# Sensors.net
KiCad netlist of a schematic drawn in Altium Designer
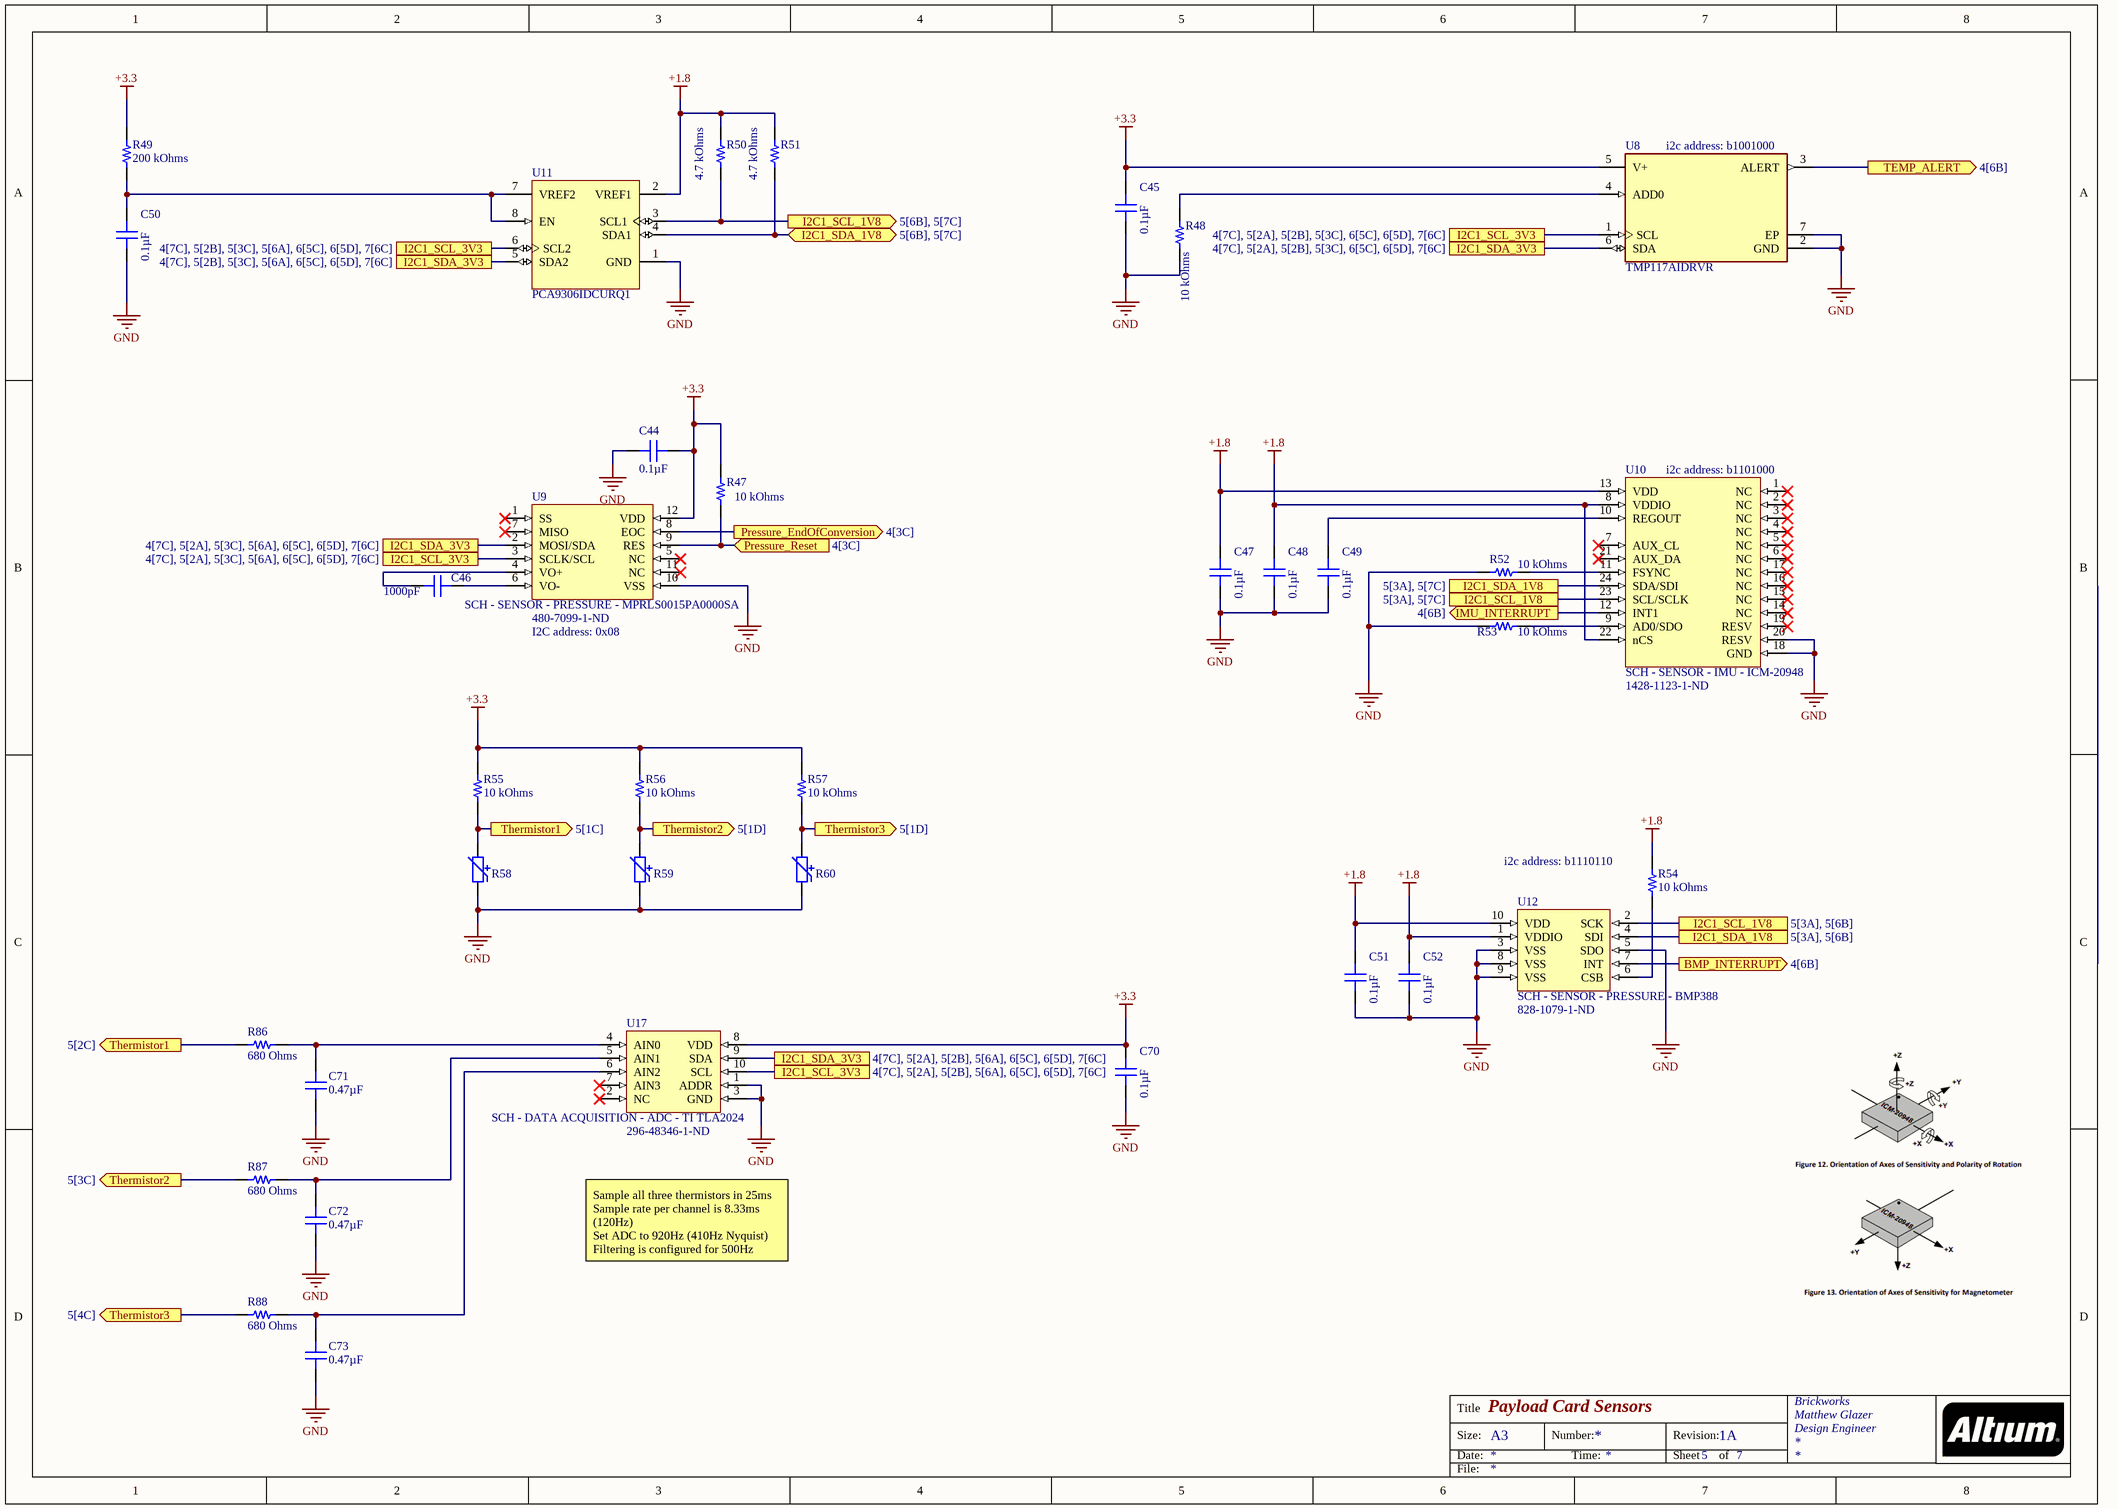
[diagram p0: Sensors.SchDoc]

(export (version "E")
  (design (tool "Eeschema 10.0.6"))
  (components
    (comp (ref "C44")
      (value "0.1µF")
      (footprint "CAP 0603_1608")
      (description "CAP CER 0.1UF 25V X7R 0603")
      (fields
        (field (name "PART NUMBER") "CL10B104KA8WPNC")
        (field (name "MANUFACTURER") "Samsung Electro-Mechanics")
      )
      (libsource (lib "Celestial Altium Library - altium_library") (part "Capacitor"))
    )
    (comp (ref "C45")
      (value "0.1µF")
      (footprint "CAP 0603_1608")
      (description "CAP CER 0.1UF 25V X7R 0603")
      (fields
        (field (name "PART NUMBER") "CL10B104KA8WPNC")
        (field (name "MANUFACTURER") "Samsung Electro-Mechanics")
      )
      (libsource (lib "Celestial Altium Library - altium_library") (part "Capacitor"))
    )
    (comp (ref "C46")
      (value "1000pF")
      (footprint "CAP 0603_1608")
      (description "CAP CER 1000PF 16V X7R 0603")
      (fields (field (name "PART NUMBER") "0603YC102JAT2A") (field (name "MANUFACTURER") "AVX Corporation"))
      (libsource (lib "Celestial Altium Library - altium_library") (part "Capacitor"))
    )
    (comp (ref "C47")
      (value "0.1µF")
      (footprint "CAP 0603_1608")
      (description "CAP CER 0.1UF 25V X7R 0603")
      (fields
        (field (name "PART NUMBER") "CL10B104KA8WPNC")
        (field (name "MANUFACTURER") "Samsung Electro-Mechanics")
      )
      (libsource (lib "Celestial Altium Library - altium_library") (part "Capacitor"))
    )
    (comp (ref "C48")
      (value "0.1µF")
      (footprint "CAP 0603_1608")
      (description "CAP CER 0.1UF 25V X7R 0603")
      (fields
        (field (name "PART NUMBER") "CL10B104KA8WPNC")
        (field (name "MANUFACTURER") "Samsung Electro-Mechanics")
      )
      (libsource (lib "Celestial Altium Library - altium_library") (part "Capacitor"))
    )
    (comp (ref "C49")
      (value "0.1µF")
      (footprint "CAP 0603_1608")
      (description "CAP CER 0.1UF 25V X7R 0603")
      (fields
        (field (name "PART NUMBER") "CL10B104KA8WPNC")
        (field (name "MANUFACTURER") "Samsung Electro-Mechanics")
      )
      (libsource (lib "Celestial Altium Library - altium_library") (part "Capacitor"))
    )
    (comp (ref "C50")
      (value "0.1µF")
      (footprint "CAP 0603_1608")
      (description "CAP CER 0.1UF 25V X7R 0603")
      (fields
        (field (name "PART NUMBER") "CL10B104KA8WPNC")
        (field (name "MANUFACTURER") "Samsung Electro-Mechanics")
      )
      (libsource (lib "Celestial Altium Library - altium_library") (part "Capacitor"))
    )
    (comp (ref "C51")
      (value "0.1µF")
      (footprint "CAP 0603_1608")
      (description "CAP CER 0.1UF 25V X7R 0603")
      (fields
        (field (name "PART NUMBER") "CL10B104KA8WPNC")
        (field (name "MANUFACTURER") "Samsung Electro-Mechanics")
      )
      (libsource (lib "Celestial Altium Library - altium_library") (part "Capacitor"))
    )
    (comp (ref "C52")
      (value "0.1µF")
      (footprint "CAP 0603_1608")
      (description "CAP CER 0.1UF 25V X7R 0603")
      (fields
        (field (name "PART NUMBER") "CL10B104KA8WPNC")
        (field (name "MANUFACTURER") "Samsung Electro-Mechanics")
      )
      (libsource (lib "Celestial Altium Library - altium_library") (part "Capacitor"))
    )
    (comp (ref "C70")
      (value "0.1µF")
      (footprint "CAP 0603_1608")
      (description "CAP CER 0.1UF 25V X7R 0603")
      (fields
        (field (name "PART NUMBER") "CL10B104KA8WPNC")
        (field (name "MANUFACTURER") "Samsung Electro-Mechanics")
      )
      (libsource (lib "Celestial Altium Library - altium_library") (part "Capacitor"))
    )
    (comp (ref "C71")
      (value "0.47µF")
      (footprint "CAP 0603_1608")
      (description "CAP CER 0.47UF 16V X5R 0603")
      (fields (field (name "PART NUMBER") "C0603C474K4PACTU") (field (name "MANUFACTURER") "KEMET"))
      (libsource (lib "Celestial Altium Library - altium_library") (part "Capacitor"))
    )
    (comp (ref "C72")
      (value "0.47µF")
      (footprint "CAP 0603_1608")
      (description "CAP CER 0.47UF 16V X5R 0603")
      (fields (field (name "PART NUMBER") "C0603C474K4PACTU") (field (name "MANUFACTURER") "KEMET"))
      (libsource (lib "Celestial Altium Library - altium_library") (part "Capacitor"))
    )
    (comp (ref "C73")
      (value "0.47µF")
      (footprint "CAP 0603_1608")
      (description "CAP CER 0.47UF 16V X5R 0603")
      (fields (field (name "PART NUMBER") "C0603C474K4PACTU") (field (name "MANUFACTURER") "KEMET"))
      (libsource (lib "Celestial Altium Library - altium_library") (part "Capacitor"))
    )
    (comp (ref "R47")
      (value "10 kOhms")
      (footprint "RES 0603_1608")
      (description "RES 10K OHM 5% 1/10W 0603")
      (fields
        (field (name "PART NUMBER") "RMCF0603JT10K0")
        (field (name "MANUFACTURER") "Stackpole Electronics Inc")
      )
      (libsource (lib "Celestial Altium Library - altium_library") (part "Resistor"))
    )
    (comp (ref "R48")
      (value "10 kOhms")
      (footprint "RES 0603_1608")
      (description "RES 10K OHM 5% 1/10W 0603")
      (fields
        (field (name "PART NUMBER") "RMCF0603JT10K0")
        (field (name "MANUFACTURER") "Stackpole Electronics Inc")
      )
      (libsource (lib "Celestial Altium Library - altium_library") (part "Resistor"))
    )
    (comp (ref "R49")
      (value "200 kOhms")
      (footprint "RES 0603_1608")
      (description "RES 200K OHM 1% 1/10W 0603")
      (fields
        (field (name "PART NUMBER") "RMCF0603FT200K")
        (field (name "MANUFACTURER") "Stackpole Electronics Inc")
      )
      (libsource (lib "Celestial Altium Library - altium_library") (part "Resistor"))
    )
    (comp (ref "R50")
      (value "4.7 kOhms")
      (footprint "RES 0603_1608")
      (description "RES 4.7K OHM 1% 1/10W 0603")
      (fields
        (field (name "PART NUMBER") "RMCF0603FT4K70")
        (field (name "MANUFACTURER") "Stackpole Electronics Inc")
      )
      (libsource (lib "Celestial Altium Library - altium_library") (part "Resistor"))
    )
    (comp (ref "R51")
      (value "4.7 kOhms")
      (footprint "RES 0603_1608")
      (description "RES 4.7K OHM 1% 1/10W 0603")
      (fields
        (field (name "PART NUMBER") "RMCF0603FT4K70")
        (field (name "MANUFACTURER") "Stackpole Electronics Inc")
      )
      (libsource (lib "Celestial Altium Library - altium_library") (part "Resistor"))
    )
    (comp (ref "R52")
      (value "10 kOhms")
      (footprint "RES 0603_1608")
      (description "RES 10K OHM 5% 1/10W 0603")
      (fields
        (field (name "PART NUMBER") "RMCF0603JT10K0")
        (field (name "MANUFACTURER") "Stackpole Electronics Inc")
      )
      (libsource (lib "Celestial Altium Library - altium_library") (part "Resistor"))
    )
    (comp (ref "R53")
      (value "10 kOhms")
      (footprint "RES 0603_1608")
      (description "RES 10K OHM 5% 1/10W 0603")
      (fields
        (field (name "PART NUMBER") "RMCF0603JT10K0")
        (field (name "MANUFACTURER") "Stackpole Electronics Inc")
      )
      (libsource (lib "Celestial Altium Library - altium_library") (part "Resistor"))
    )
    (comp (ref "R54")
      (value "10 kOhms")
      (footprint "RES 0603_1608")
      (description "RES 10K OHM 5% 1/10W 0603")
      (fields
        (field (name "PART NUMBER") "RMCF0603JT10K0")
        (field (name "MANUFACTURER") "Stackpole Electronics Inc")
      )
      (libsource (lib "Celestial Altium Library - altium_library") (part "Resistor"))
    )
    (comp (ref "R55")
      (value "10 kOhms")
      (footprint "RES 0603_1608")
      (description "RES 10K OHM 1% 1/10W 0603")
      (fields
        (field (name "PART NUMBER") "RMCF0603FT10K0")
        (field (name "MANUFACTURER") "Stackpole Electronics Inc")
      )
      (libsource (lib "Celestial Altium Library - altium_library") (part "Resistor"))
    )
    (comp (ref "R56")
      (value "10 kOhms")
      (footprint "RES 0603_1608")
      (description "RES 10K OHM 1% 1/10W 0603")
      (fields
        (field (name "PART NUMBER") "RMCF0603FT10K0")
        (field (name "MANUFACTURER") "Stackpole Electronics Inc")
      )
      (libsource (lib "Celestial Altium Library - altium_library") (part "Resistor"))
    )
    (comp (ref "R57")
      (value "10 kOhms")
      (footprint "RES 0603_1608")
      (description "RES 10K OHM 1% 1/10W 0603")
      (fields
        (field (name "PART NUMBER") "RMCF0603FT10K0")
        (field (name "MANUFACTURER") "Stackpole Electronics Inc")
      )
      (libsource (lib "Celestial Altium Library - altium_library") (part "Resistor"))
    )
    (comp (ref "R58")
      (value "10 kOhms")
      (footprint "PTC 0402_1005")
      (description "SENSOR PTC 10KOHM 1% X1SON")
      (fields (field (name "MANUFACTURER") "Texas Instruments") (field (name "PART NUMBER") "TMP6131DECR"))
      (libsource (lib "Celestial Altium Library - altium_library") (part "Thermistor PTC"))
    )
    (comp (ref "R59")
      (value "10 kOhms")
      (footprint "PTC 0402_1005")
      (description "SENSOR PTC 10KOHM 1% X1SON")
      (fields (field (name "MANUFACTURER") "Texas Instruments") (field (name "PART NUMBER") "TMP6131DECR"))
      (libsource (lib "Celestial Altium Library - altium_library") (part "Thermistor PTC"))
    )
    (comp (ref "R60")
      (value "10 kOhms")
      (footprint "PTC 0402_1005")
      (description "SENSOR PTC 10KOHM 1% X1SON")
      (fields (field (name "MANUFACTURER") "Texas Instruments") (field (name "PART NUMBER") "TMP6131DECR"))
      (libsource (lib "Celestial Altium Library - altium_library") (part "Thermistor PTC"))
    )
    (comp (ref "R86")
      (value "680 Ohms")
      (footprint "RES 0603_1608")
      (description "RES 680 OHM 1% 1/10W 0603")
      (fields
        (field (name "PART NUMBER") "RMCF0603FT680R")
        (field (name "MANUFACTURER") "Stackpole Electronics Inc")
      )
      (libsource (lib "Celestial Altium Library - altium_library") (part "Resistor"))
    )
    (comp (ref "R87")
      (value "680 Ohms")
      (footprint "RES 0603_1608")
      (description "RES 680 OHM 1% 1/10W 0603")
      (fields
        (field (name "PART NUMBER") "RMCF0603FT680R")
        (field (name "MANUFACTURER") "Stackpole Electronics Inc")
      )
      (libsource (lib "Celestial Altium Library - altium_library") (part "Resistor"))
    )
    (comp (ref "R88")
      (value "680 Ohms")
      (footprint "RES 0603_1608")
      (description "RES 680 OHM 1% 1/10W 0603")
      (fields
        (field (name "PART NUMBER") "RMCF0603FT680R")
        (field (name "MANUFACTURER") "Stackpole Electronics Inc")
      )
      (libsource (lib "Celestial Altium Library - altium_library") (part "Resistor"))
    )
    (comp (ref "U8")
      (value "TMP117AIDRVR")
      (footprint "FP-DRV0006A-MFG")
      (description "TEMPERATURE SENSOR")
      (fields
        (field (name "OCTOPART") "https://octopart.com/tmp117aidrvr-texas+instruments-95511044")
        (field (name "MANUFACTURER") "Texas Instruments")
      )
      (libsource (lib "Altium Content Vault") (part "bceab6869a9cb85cf5675529ee35ce4"))
    )
    (comp (ref "U9")
      (value "SCH - SENSOR - PRESSURE - MPRLS0015PA0000SA")
      (footprint "PCB - LEADLESS - SMD - Honeywell SMD12")
      (fields (field (name "SUPPLIER PART NUMBER 1") "480-7099-1-ND"))
      (libsource (lib "HAB_ICs") (part "SCH - SENSOR - PRESSURE - MPRLS0015PA0000SA"))
    )
    (comp (ref "U10")
      (value "SCH - SENSOR - IMU - ICM-20948")
      (footprint "PCB - LEADLESS - QFN - TDK 24-TFQFN")
      (fields (field (name "SUPPLIER PART NUMBER 1") "1428-1123-1-ND"))
      (libsource (lib "HAB_ICs") (part "SCH - SENSOR - IMU - ICM-20948"))
    )
    (comp (ref "U11")
      (value "PCA9306IDCURQ1")
      (footprint "DCU0008A_M")
      (fields (field (name "MANUFACTURER") "Texas Instruments"))
      (libsource (lib "Altium Content Vault") (part "TI-PCA9306-Q1-US8_DCU-8"))
    )
    (comp (ref "U12")
      (value "SCH - SENSOR - PRESSURE - BMP388")
      (footprint "PCB - LEADLESS - BOSCH LGA10")
      (fields (field (name "SUPPLIER PART NUMBER 1") "828-1079-1-ND"))
      (libsource (lib "HAB_ICs") (part "SCH - SENSOR - PRESSURE - BMP388"))
    )
    (comp (ref "U17")
      (value "SCH - DATA ACQUISITION - ADC - TI TLA2024")
      (footprint "PCB - LEADLESS - QFN - TI X2QFN-10")
      (fields (field (name "SUPPLIER PART NUMBER 1") "296-48346-1-ND"))
      (libsource (lib "HAB_ICs") (part "SCH - DATA ACQUISITION - ADC - TI TLA2024"))
    )
  )
  (nets
    (net (code "1") (name "+1.8") (class "Default")
      (node (ref "C47") (pin "2") (pinfunction "2_2") (pintype "passive"))
      (node (ref "C48") (pin "2") (pinfunction "2_2") (pintype "passive"))
      (node (ref "C51") (pin "2") (pinfunction "2_2") (pintype "passive"))
      (node (ref "C52") (pin "2") (pinfunction "2_2") (pintype "passive"))
      (node (ref "R50") (pin "2") (pinfunction "2_2") (pintype "passive"))
      (node (ref "R51") (pin "2") (pinfunction "2_2") (pintype "passive"))
      (node (ref "R54") (pin "1") (pinfunction "1_1") (pintype "passive"))
      (node (ref "U10") (pin "13") (pinfunction "VDD_13") (pintype "input"))
      (node (ref "U10") (pin "22") (pinfunction "nCS_22") (pintype "input"))
      (node (ref "U10") (pin "8") (pinfunction "VDDIO_8") (pintype "input"))
      (node (ref "U11") (pin "2") (pinfunction "VREF1_2") (pintype "power_in"))
      (node (ref "U12") (pin "1") (pinfunction "VDDIO_1") (pintype "input"))
      (node (ref "U12") (pin "10") (pinfunction "VDD_10") (pintype "input"))
    )
    (net (code "2") (name "+3.3") (class "Default")
      (node (ref "C44") (pin "1") (pinfunction "1_1") (pintype "passive"))
      (node (ref "C45") (pin "2") (pinfunction "2_2") (pintype "passive"))
      (node (ref "C70") (pin "2") (pinfunction "2_2") (pintype "passive"))
      (node (ref "R47") (pin "2") (pinfunction "2_2") (pintype "passive"))
      (node (ref "R49") (pin "2") (pinfunction "2_2") (pintype "passive"))
      (node (ref "R55") (pin "2") (pinfunction "2_2") (pintype "passive"))
      (node (ref "R56") (pin "2") (pinfunction "2_2") (pintype "passive"))
      (node (ref "R57") (pin "2") (pinfunction "2_2") (pintype "passive"))
      (node (ref "U17") (pin "8") (pinfunction "VDD_8") (pintype "input"))
      (node (ref "U8") (pin "5") (pinfunction "V+_5") (pintype "power_in"))
      (node (ref "U9") (pin "12") (pinfunction "VDD_12") (pintype "input"))
    )
    (net (code "3") (name "/BMP_INTERRUPT") (class "Default")
      (node (ref "U12") (pin "7") (pinfunction "INT_7") (pintype "input"))
    )
    (net (code "4") (name "/I2C1_SCL_1V8") (class "Default")
      (node (ref "R50") (pin "1") (pinfunction "1_1") (pintype "passive"))
      (node (ref "U10") (pin "23") (pinfunction "SCL/SCLK_23") (pintype "input"))
      (node (ref "U11") (pin "3") (pinfunction "SCL1_3") (pintype "bidirectional"))
      (node (ref "U12") (pin "2") (pinfunction "SCK_2") (pintype "input"))
    )
    (net (code "5") (name "/I2C1_SCL_3V3") (class "Default")
      (node (ref "U11") (pin "6") (pinfunction "SCL2_6") (pintype "bidirectional"))
      (node (ref "U17") (pin "10") (pinfunction "SCL_10") (pintype "input"))
      (node (ref "U8") (pin "1") (pinfunction "SCL_1") (pintype "input"))
      (node (ref "U9") (pin "3") (pinfunction "SCLK/SCL_3") (pintype "input"))
    )
    (net (code "6") (name "/I2C1_SDA_1V8") (class "Default")
      (node (ref "R51") (pin "1") (pinfunction "1_1") (pintype "passive"))
      (node (ref "U10") (pin "24") (pinfunction "SDA/SDI_24") (pintype "input"))
      (node (ref "U11") (pin "4") (pinfunction "SDA1_4") (pintype "bidirectional"))
      (node (ref "U12") (pin "4") (pinfunction "SDI_4") (pintype "input"))
    )
    (net (code "7") (name "/I2C1_SDA_3V3") (class "Default")
      (node (ref "U11") (pin "5") (pinfunction "SDA2_5") (pintype "bidirectional"))
      (node (ref "U17") (pin "9") (pinfunction "SDA_9") (pintype "input"))
      (node (ref "U8") (pin "6") (pinfunction "SDA_6") (pintype "bidirectional"))
      (node (ref "U9") (pin "2") (pinfunction "MOSI/SDA_2") (pintype "input"))
    )
    (net (code "8") (name "/IMU_INTERRUPT") (class "Default")
      (node (ref "U10") (pin "12") (pinfunction "INT1_12") (pintype "input"))
    )
    (net (code "9") (name "/Pressure_EndOfConversion") (class "Default")
      (node (ref "U9") (pin "8") (pinfunction "EOC_8") (pintype "input"))
    )
    (net (code "10") (name "/Pressure_Reset") (class "Default")
      (node (ref "R47") (pin "1") (pinfunction "1_1") (pintype "passive"))
      (node (ref "U9") (pin "9") (pinfunction "RES_9") (pintype "input"))
    )
    (net (code "11") (name "/TEMP_ALERT") (class "Default")
      (node (ref "U8") (pin "3") (pinfunction "ALERT_3") (pintype "output"))
    )
    (net (code "12") (name "/Thermistor1") (class "Default")
      (node (ref "R55") (pin "1") (pinfunction "1_1") (pintype "passive"))
      (node (ref "R58") (pin "2") (pinfunction "2_2") (pintype "passive"))
      (node (ref "R86") (pin "1") (pinfunction "1_1") (pintype "passive"))
    )
    (net (code "13") (name "/Thermistor2") (class "Default")
      (node (ref "R56") (pin "1") (pinfunction "1_1") (pintype "passive"))
      (node (ref "R59") (pin "2") (pinfunction "2_2") (pintype "passive"))
      (node (ref "R87") (pin "1") (pinfunction "1_1") (pintype "passive"))
    )
    (net (code "14") (name "/Thermistor3") (class "Default")
      (node (ref "R57") (pin "1") (pinfunction "1_1") (pintype "passive"))
      (node (ref "R60") (pin "2") (pinfunction "2_2") (pintype "passive"))
      (node (ref "R88") (pin "1") (pinfunction "1_1") (pintype "passive"))
    )
    (net (code "15") (name "GND") (class "Default")
      (node (ref "C44") (pin "2") (pinfunction "2_2") (pintype "passive"))
      (node (ref "C45") (pin "1") (pinfunction "1_1") (pintype "passive"))
      (node (ref "C47") (pin "1") (pinfunction "1_1") (pintype "passive"))
      (node (ref "C48") (pin "1") (pinfunction "1_1") (pintype "passive"))
      (node (ref "C49") (pin "1") (pinfunction "1_1") (pintype "passive"))
      (node (ref "C50") (pin "1") (pinfunction "1_1") (pintype "passive"))
      (node (ref "C51") (pin "1") (pinfunction "1_1") (pintype "passive"))
      (node (ref "C52") (pin "1") (pinfunction "1_1") (pintype "passive"))
      (node (ref "C70") (pin "1") (pinfunction "1_1") (pintype "passive"))
      (node (ref "C71") (pin "1") (pinfunction "1_1") (pintype "passive"))
      (node (ref "C72") (pin "1") (pinfunction "1_1") (pintype "passive"))
      (node (ref "C73") (pin "1") (pinfunction "1_1") (pintype "passive"))
      (node (ref "R48") (pin "1") (pinfunction "1_1") (pintype "passive"))
      (node (ref "R52") (pin "2") (pinfunction "2_2") (pintype "passive"))
      (node (ref "R53") (pin "2") (pinfunction "2_2") (pintype "passive"))
      (node (ref "R58") (pin "1") (pinfunction "1_1") (pintype "passive"))
      (node (ref "R59") (pin "1") (pinfunction "1_1") (pintype "passive"))
      (node (ref "R60") (pin "1") (pinfunction "1_1") (pintype "passive"))
      (node (ref "U10") (pin "18") (pinfunction "GND_18") (pintype "input"))
      (node (ref "U10") (pin "20") (pinfunction "RESV_20") (pintype "input"))
      (node (ref "U11") (pin "1") (pinfunction "GND_1") (pintype "power_in"))
      (node (ref "U12") (pin "3") (pinfunction "VSS_3") (pintype "input"))
      (node (ref "U12") (pin "5") (pinfunction "SDO_5") (pintype "input"))
      (node (ref "U12") (pin "8") (pinfunction "VSS_8") (pintype "input"))
      (node (ref "U12") (pin "9") (pinfunction "VSS_9") (pintype "input"))
      (node (ref "U17") (pin "1") (pinfunction "ADDR_1") (pintype "input"))
      (node (ref "U17") (pin "3") (pinfunction "GND_3") (pintype "input"))
      (node (ref "U8") (pin "2") (pinfunction "GND_2") (pintype "power_in"))
      (node (ref "U8") (pin "7") (pinfunction "EP_7") (pintype "passive"))
      (node (ref "U9") (pin "10") (pinfunction "VSS_10") (pintype "input"))
    )
    (net (code "16") (name "Net-(U8-ADD0)") (class "Default")
      (node (ref "R48") (pin "2") (pinfunction "2_2") (pintype "passive"))
      (node (ref "U8") (pin "4") (pinfunction "ADD0_4") (pintype "input"))
    )
    (net (code "17") (name "Net-(U9-VO+)") (class "Default")
      (node (ref "C46") (pin "1") (pinfunction "1_1") (pintype "passive"))
      (node (ref "U9") (pin "4") (pinfunction "VO+_4") (pintype "input"))
    )
    (net (code "18") (name "Net-(U9-VO-)") (class "Default")
      (node (ref "C46") (pin "2") (pinfunction "2_2") (pintype "passive"))
      (node (ref "U9") (pin "6") (pinfunction "VO-_6") (pintype "input"))
    )
    (net (code "19") (name "Net-(U10-AD0{slash}SDO)") (class "Default")
      (node (ref "R53") (pin "1") (pinfunction "1_1") (pintype "passive"))
      (node (ref "U10") (pin "9") (pinfunction "AD0/SDO_9") (pintype "input"))
    )
    (net (code "20") (name "Net-(U10-FSYNC)") (class "Default")
      (node (ref "R52") (pin "1") (pinfunction "1_1") (pintype "passive"))
      (node (ref "U10") (pin "11") (pinfunction "FSYNC_11") (pintype "input"))
    )
    (net (code "21") (name "Net-(U10-REGOUT)") (class "Default")
      (node (ref "C49") (pin "2") (pinfunction "2_2") (pintype "passive"))
      (node (ref "U10") (pin "10") (pinfunction "REGOUT_10") (pintype "input"))
    )
    (net (code "22") (name "Net-(U11-EN)") (class "Default")
      (node (ref "C50") (pin "2") (pinfunction "2_2") (pintype "passive"))
      (node (ref "R49") (pin "1") (pinfunction "1_1") (pintype "passive"))
      (node (ref "U11") (pin "7") (pinfunction "VREF2_7") (pintype "power_in"))
      (node (ref "U11") (pin "8") (pinfunction "EN_8") (pintype "input"))
    )
    (net (code "23") (name "Net-(U12-CSB)") (class "Default")
      (node (ref "R54") (pin "2") (pinfunction "2_2") (pintype "passive"))
      (node (ref "U12") (pin "6") (pinfunction "CSB_6") (pintype "input"))
    )
    (net (code "24") (name "Net-(U17-AIN0)") (class "Default")
      (node (ref "C71") (pin "2") (pinfunction "2_2") (pintype "passive"))
      (node (ref "R86") (pin "2") (pinfunction "2_2") (pintype "passive"))
      (node (ref "U17") (pin "4") (pinfunction "AIN0_4") (pintype "input"))
    )
    (net (code "25") (name "Net-(U17-AIN1)") (class "Default")
      (node (ref "C72") (pin "2") (pinfunction "2_2") (pintype "passive"))
      (node (ref "R87") (pin "2") (pinfunction "2_2") (pintype "passive"))
      (node (ref "U17") (pin "5") (pinfunction "AIN1_5") (pintype "input"))
    )
    (net (code "26") (name "Net-(U17-AIN2)") (class "Default")
      (node (ref "C73") (pin "2") (pinfunction "2_2") (pintype "passive"))
      (node (ref "R88") (pin "2") (pinfunction "2_2") (pintype "passive"))
      (node (ref "U17") (pin "6") (pinfunction "AIN2_6") (pintype "input"))
    )
    (net (code "27") (name "unconnected-(U9-MISO-Pad7)") (class "Default")
      (node (ref "U9") (pin "7") (pinfunction "MISO_7") (pintype "input+no_connect"))
    )
    (net (code "28") (name "unconnected-(U9-NC-Pad5)") (class "Default")
      (node (ref "U9") (pin "5") (pinfunction "NC_5") (pintype "input+no_connect"))
    )
    (net (code "29") (name "unconnected-(U9-NC-Pad11)") (class "Default")
      (node (ref "U9") (pin "11") (pinfunction "NC_11") (pintype "input+no_connect"))
    )
    (net (code "30") (name "unconnected-(U9-SS-Pad1)") (class "Default")
      (node (ref "U9") (pin "1") (pinfunction "SS_1") (pintype "input+no_connect"))
    )
    (net (code "31") (name "unconnected-(U10-AUX_CL-Pad7)") (class "Default")
      (node (ref "U10") (pin "7") (pinfunction "AUX_CL_7") (pintype "input+no_connect"))
    )
    (net (code "32") (name "unconnected-(U10-AUX_DA-Pad21)") (class "Default")
      (node (ref "U10") (pin "21") (pinfunction "AUX_DA_21") (pintype "input+no_connect"))
    )
    (net (code "33") (name "unconnected-(U10-NC-Pad1)") (class "Default")
      (node (ref "U10") (pin "1") (pinfunction "NC_1") (pintype "input+no_connect"))
    )
    (net (code "34") (name "unconnected-(U10-NC-Pad2)") (class "Default")
      (node (ref "U10") (pin "2") (pinfunction "NC_2") (pintype "input+no_connect"))
    )
    (net (code "35") (name "unconnected-(U10-NC-Pad3)") (class "Default")
      (node (ref "U10") (pin "3") (pinfunction "NC_3") (pintype "input+no_connect"))
    )
    (net (code "36") (name "unconnected-(U10-NC-Pad4)") (class "Default")
      (node (ref "U10") (pin "4") (pinfunction "NC_4") (pintype "input+no_connect"))
    )
    (net (code "37") (name "unconnected-(U10-NC-Pad5)") (class "Default")
      (node (ref "U10") (pin "5") (pinfunction "NC_5") (pintype "input+no_connect"))
    )
    (net (code "38") (name "unconnected-(U10-NC-Pad6)") (class "Default")
      (node (ref "U10") (pin "6") (pinfunction "NC_6") (pintype "input+no_connect"))
    )
    (net (code "39") (name "unconnected-(U10-NC-Pad14)") (class "Default")
      (node (ref "U10") (pin "14") (pinfunction "NC_14") (pintype "input+no_connect"))
    )
    (net (code "40") (name "unconnected-(U10-NC-Pad15)") (class "Default")
      (node (ref "U10") (pin "15") (pinfunction "NC_15") (pintype "input+no_connect"))
    )
    (net (code "41") (name "unconnected-(U10-NC-Pad16)") (class "Default")
      (node (ref "U10") (pin "16") (pinfunction "NC_16") (pintype "input+no_connect"))
    )
    (net (code "42") (name "unconnected-(U10-NC-Pad17)") (class "Default")
      (node (ref "U10") (pin "17") (pinfunction "NC_17") (pintype "input+no_connect"))
    )
    (net (code "43") (name "unconnected-(U10-RESV-Pad19)") (class "Default")
      (node (ref "U10") (pin "19") (pinfunction "RESV_19") (pintype "input+no_connect"))
    )
    (net (code "44") (name "unconnected-(U17-AIN3-Pad7)") (class "Default")
      (node (ref "U17") (pin "7") (pinfunction "AIN3_7") (pintype "input+no_connect"))
    )
    (net (code "45") (name "unconnected-(U17-NC-Pad2)") (class "Default")
      (node (ref "U17") (pin "2") (pinfunction "NC_2") (pintype "input+no_connect"))
    )
  )
)
